# Pro_Trinket_Keyboard_V2.net
KiCad netlist of a schematic drawn in EAGLE
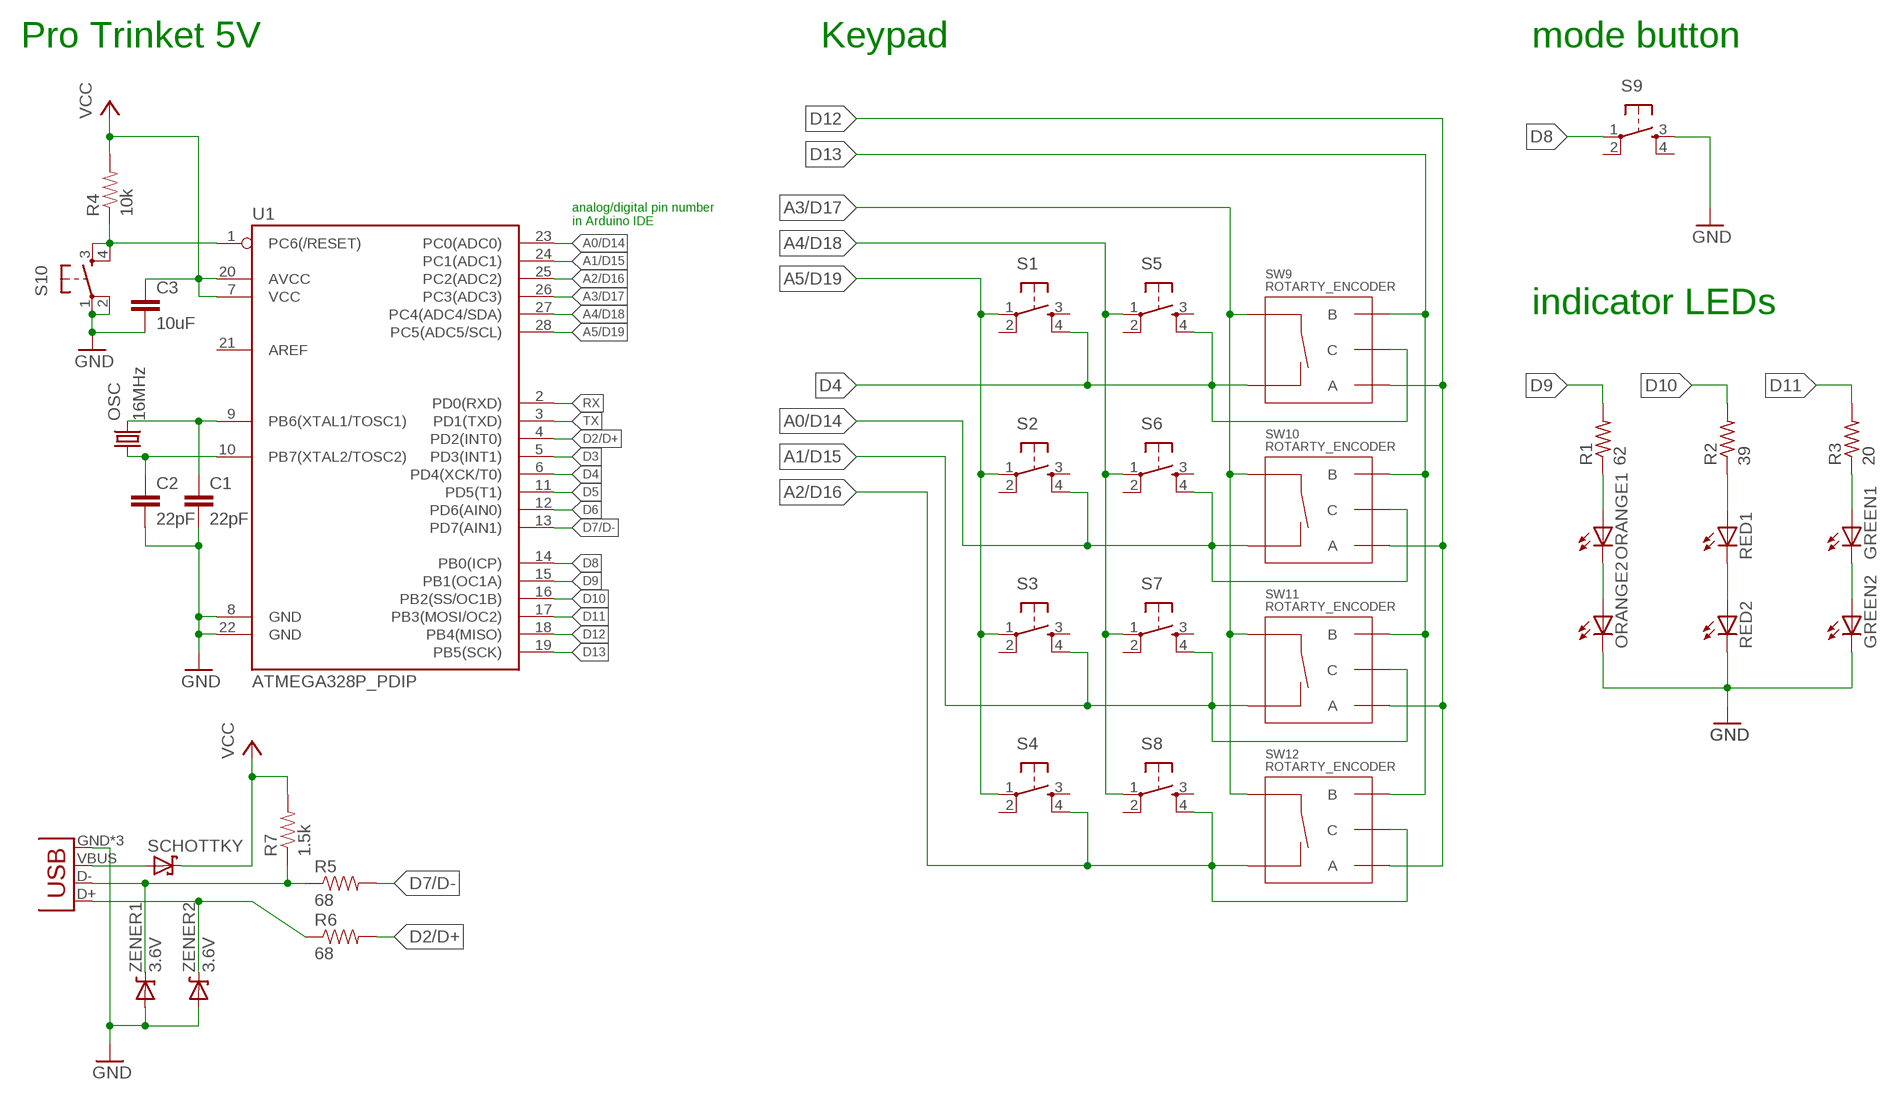
[diagram p0: schematic, sheet 1]

(export (version "E")
  (design (tool "Eeschema 10.0.6"))
  (components
    (comp (ref "C1")
      (value "22pF")
      (footprint "eagle-import:0603-CAP")
      (libsource (lib "eagle-import") (part "22PF-50V-5%(0603)"))
    )
    (comp (ref "C2")
      (value "22pF")
      (footprint "eagle-import:0603-CAP")
      (libsource (lib "eagle-import") (part "22PF-50V-5%(0603)"))
    )
    (comp (ref "C3")
      (value "10uF")
      (footprint "eagle-import:0603-CAP")
      (libsource (lib "eagle-import") (part "10UF-6.3V-20%(0603)"))
    )
    (comp (ref "GREEN1")
      (value "LED3MM")
      (footprint "eagle-import:LED3MM")
      (libsource (lib "eagle-import") (part "LED3MM"))
    )
    (comp (ref "GREEN2")
      (value "LED3MM")
      (footprint "eagle-import:LED3MM")
      (libsource (lib "eagle-import") (part "LED3MM"))
    )
    (comp (ref "JP1")
      (value "USB-MICROB")
      (footprint "eagle-import:USB-MICROB")
      (libsource (lib "eagle-import") (part "USB-MICROB"))
    )
    (comp (ref "ORANGE1")
      (value "LED3MM")
      (footprint "eagle-import:LED3MM")
      (libsource (lib "eagle-import") (part "LED3MM"))
    )
    (comp (ref "ORANGE2")
      (value "LED3MM")
      (footprint "eagle-import:LED3MM")
      (libsource (lib "eagle-import") (part "LED3MM"))
    )
    (comp (ref "OSC")
      (value "16MHz")
      (footprint "eagle-import:HC49_S")
      (libsource (lib "eagle-import") (part "CRYSTALHC49S"))
    )
    (comp (ref "R1")
      (value "62")
      (footprint "eagle-import:0204_7")
      (libsource (lib "eagle-import") (part "R-US_0204/7"))
    )
    (comp (ref "R2")
      (value "39")
      (footprint "eagle-import:0204_7")
      (libsource (lib "eagle-import") (part "R-US_0204/7"))
    )
    (comp (ref "R3")
      (value "20")
      (footprint "eagle-import:0204_7")
      (libsource (lib "eagle-import") (part "R-US_0204/7"))
    )
    (comp (ref "R4")
      (value "10k")
      (footprint "eagle-import:0805")
      (libsource (lib "eagle-import") (part "RESISTOR0805-RES"))
    )
    (comp (ref "R5")
      (value "68")
      (footprint "eagle-import:0805")
      (libsource (lib "eagle-import") (part "RESISTOR0805-RES"))
    )
    (comp (ref "R6")
      (value "68")
      (footprint "eagle-import:0805")
      (libsource (lib "eagle-import") (part "RESISTOR0805-RES"))
    )
    (comp (ref "R7")
      (value "1.5k")
      (footprint "eagle-import:0805")
      (libsource (lib "eagle-import") (part "RESISTOR0805-RES"))
    )
    (comp (ref "RED1")
      (value "LED3MM")
      (footprint "eagle-import:LED3MM")
      (libsource (lib "eagle-import") (part "LED3MM"))
    )
    (comp (ref "RED2")
      (value "LED3MM")
      (footprint "eagle-import:LED3MM")
      (libsource (lib "eagle-import") (part "LED3MM"))
    )
    (comp (ref "S1")
      (value "TAC_SWITCHPTH")
      (footprint "eagle-import:TACTILE-PTH")
      (libsource (lib "eagle-import") (part "TAC_SWITCHPTH"))
    )
    (comp (ref "S2")
      (value "TAC_SWITCHPTH")
      (footprint "eagle-import:TACTILE-PTH")
      (libsource (lib "eagle-import") (part "TAC_SWITCHPTH"))
    )
    (comp (ref "S3")
      (value "TAC_SWITCHPTH")
      (footprint "eagle-import:TACTILE-PTH")
      (libsource (lib "eagle-import") (part "TAC_SWITCHPTH"))
    )
    (comp (ref "S4")
      (value "TAC_SWITCHPTH")
      (footprint "eagle-import:TACTILE-PTH")
      (libsource (lib "eagle-import") (part "TAC_SWITCHPTH"))
    )
    (comp (ref "S5")
      (value "TAC_SWITCHPTH")
      (footprint "eagle-import:TACTILE-PTH")
      (libsource (lib "eagle-import") (part "TAC_SWITCHPTH"))
    )
    (comp (ref "S6")
      (value "TAC_SWITCHPTH")
      (footprint "eagle-import:TACTILE-PTH")
      (libsource (lib "eagle-import") (part "TAC_SWITCHPTH"))
    )
    (comp (ref "S7")
      (value "TAC_SWITCHPTH")
      (footprint "eagle-import:TACTILE-PTH")
      (libsource (lib "eagle-import") (part "TAC_SWITCHPTH"))
    )
    (comp (ref "S8")
      (value "TAC_SWITCHPTH")
      (footprint "eagle-import:TACTILE-PTH")
      (libsource (lib "eagle-import") (part "TAC_SWITCHPTH"))
    )
    (comp (ref "S9")
      (value "TAC_SWITCHPTH")
      (footprint "eagle-import:TACTILE-PTH")
      (libsource (lib "eagle-import") (part "TAC_SWITCHPTH"))
    )
    (comp (ref "S10")
      (value "TAC_SWITCHPTH")
      (footprint "eagle-import:TACTILE-PTH")
      (libsource (lib "eagle-import") (part "TAC_SWITCHPTH"))
    )
    (comp (ref "SCHOTTKY")
      (value "SCHOTTKY-DIODEAG")
      (footprint "eagle-import:AG")
      (libsource (lib "eagle-import") (part "SCHOTTKY-DIODEAG"))
    )
    (comp (ref "SW9")
      (value "ROTARTY_ENCODER")
      (footprint "eagle-import:ROTARY_ENC_PLAIN")
      (libsource (lib "eagle-import") (part "ROTARTY_ENCODER"))
    )
    (comp (ref "SW10")
      (value "ROTARTY_ENCODER")
      (footprint "eagle-import:ROTARY_ENC_PLAIN")
      (libsource (lib "eagle-import") (part "ROTARTY_ENCODER"))
    )
    (comp (ref "SW11")
      (value "ROTARTY_ENCODER")
      (footprint "eagle-import:ROTARY_ENC_PLAIN")
      (libsource (lib "eagle-import") (part "ROTARTY_ENCODER"))
    )
    (comp (ref "SW12")
      (value "ROTARTY_ENCODER")
      (footprint "eagle-import:ROTARY_ENC_PLAIN")
      (libsource (lib "eagle-import") (part "ROTARTY_ENCODER"))
    )
    (comp (ref "U1")
      (value "ATMEGA328P_PDIP")
      (footprint "eagle-import:DIL28-3")
      (libsource (lib "eagle-import") (part "ATMEGA328P_PDIP"))
    )
    (comp (ref "ZENER1")
      (value "3.6V")
      (footprint "eagle-import:SOD-323")
      (libsource (lib "eagle-import") (part "DIODE-ZENER-BZT52"))
    )
    (comp (ref "ZENER2")
      (value "3.6V")
      (footprint "eagle-import:SOD-323")
      (libsource (lib "eagle-import") (part "DIODE-ZENER-BZT52"))
    )
  )
  (nets
    (net (code "1") (name "A0{slash}D14") (class "Default")
      (node (ref "S2") (pin "4") (pinfunction "4_4") (pintype "passive"))
      (node (ref "S6") (pin "4") (pinfunction "4_4") (pintype "passive"))
      (node (ref "SW10") (pin "C") (pinfunction "C_C") (pintype "bidirectional"))
      (node (ref "SW10") (pin "SW-") (pinfunction "SW-_SW-") (pintype "bidirectional"))
      (node (ref "U1") (pin "23") (pinfunction "PC0(ADC0)_23") (pintype "bidirectional"))
    )
    (net (code "2") (name "A1{slash}D15") (class "Default")
      (node (ref "S3") (pin "4") (pinfunction "4_4") (pintype "passive"))
      (node (ref "S7") (pin "4") (pinfunction "4_4") (pintype "passive"))
      (node (ref "SW11") (pin "C") (pinfunction "C_C") (pintype "bidirectional"))
      (node (ref "SW11") (pin "SW-") (pinfunction "SW-_SW-") (pintype "bidirectional"))
      (node (ref "U1") (pin "24") (pinfunction "PC1(ADC1)_24") (pintype "bidirectional"))
    )
    (net (code "3") (name "A2{slash}D16") (class "Default")
      (node (ref "S4") (pin "4") (pinfunction "4_4") (pintype "passive"))
      (node (ref "S8") (pin "4") (pinfunction "4_4") (pintype "passive"))
      (node (ref "SW12") (pin "C") (pinfunction "C_C") (pintype "bidirectional"))
      (node (ref "SW12") (pin "SW-") (pinfunction "SW-_SW-") (pintype "bidirectional"))
      (node (ref "U1") (pin "25") (pinfunction "PC2(ADC2)_25") (pintype "bidirectional"))
    )
    (net (code "4") (name "A3{slash}D17") (class "Default")
      (node (ref "SW10") (pin "SW+") (pinfunction "SW+_SW+") (pintype "bidirectional"))
      (node (ref "SW11") (pin "SW+") (pinfunction "SW+_SW+") (pintype "bidirectional"))
      (node (ref "SW12") (pin "SW+") (pinfunction "SW+_SW+") (pintype "bidirectional"))
      (node (ref "SW9") (pin "SW+") (pinfunction "SW+_SW+") (pintype "bidirectional"))
      (node (ref "U1") (pin "26") (pinfunction "PC3(ADC3)_26") (pintype "bidirectional"))
    )
    (net (code "5") (name "A4{slash}D18") (class "Default")
      (node (ref "S5") (pin "1") (pinfunction "1_1") (pintype "passive"))
      (node (ref "S6") (pin "1") (pinfunction "1_1") (pintype "passive"))
      (node (ref "S7") (pin "1") (pinfunction "1_1") (pintype "passive"))
      (node (ref "S8") (pin "1") (pinfunction "1_1") (pintype "passive"))
      (node (ref "U1") (pin "27") (pinfunction "PC4(ADC4/SDA)_27") (pintype "bidirectional"))
    )
    (net (code "6") (name "A5{slash}D19") (class "Default")
      (node (ref "S1") (pin "1") (pinfunction "1_1") (pintype "passive"))
      (node (ref "S2") (pin "1") (pinfunction "1_1") (pintype "passive"))
      (node (ref "S3") (pin "1") (pinfunction "1_1") (pintype "passive"))
      (node (ref "S4") (pin "1") (pinfunction "1_1") (pintype "passive"))
      (node (ref "U1") (pin "28") (pinfunction "PC5(ADC5/SCL)_28") (pintype "bidirectional"))
    )
    (net (code "7") (name "D2{slash}D+") (class "Default")
      (node (ref "R6") (pin "2") (pinfunction "2_2") (pintype "passive"))
      (node (ref "U1") (pin "4") (pinfunction "PD2(INT0)_4") (pintype "bidirectional"))
    )
    (net (code "8") (name "D3") (class "Default")
      (node (ref "U1") (pin "5") (pinfunction "PD3(INT1)_5") (pintype "bidirectional"))
    )
    (net (code "9") (name "D4") (class "Default")
      (node (ref "S1") (pin "4") (pinfunction "4_4") (pintype "passive"))
      (node (ref "S5") (pin "4") (pinfunction "4_4") (pintype "passive"))
      (node (ref "SW9") (pin "C") (pinfunction "C_C") (pintype "bidirectional"))
      (node (ref "SW9") (pin "SW-") (pinfunction "SW-_SW-") (pintype "bidirectional"))
      (node (ref "U1") (pin "6") (pinfunction "PD4(XCK/T0)_6") (pintype "bidirectional"))
    )
    (net (code "10") (name "D5") (class "Default")
      (node (ref "U1") (pin "11") (pinfunction "PD5(T1)_11") (pintype "bidirectional"))
    )
    (net (code "11") (name "D6") (class "Default")
      (node (ref "U1") (pin "12") (pinfunction "PD6(AIN0)_12") (pintype "bidirectional"))
    )
    (net (code "12") (name "D7{slash}D-") (class "Default")
      (node (ref "R5") (pin "2") (pinfunction "2_2") (pintype "passive"))
      (node (ref "U1") (pin "13") (pinfunction "PD7(AIN1)_13") (pintype "bidirectional"))
    )
    (net (code "13") (name "D8") (class "Default")
      (node (ref "S9") (pin "1") (pinfunction "1_1") (pintype "passive"))
      (node (ref "U1") (pin "14") (pinfunction "PB0(ICP)_14") (pintype "bidirectional"))
    )
    (net (code "14") (name "D9") (class "Default")
      (node (ref "R1") (pin "2") (pinfunction "2_2") (pintype "passive"))
      (node (ref "U1") (pin "15") (pinfunction "PB1(OC1A)_15") (pintype "bidirectional"))
    )
    (net (code "15") (name "D10") (class "Default")
      (node (ref "R2") (pin "2") (pinfunction "2_2") (pintype "passive"))
      (node (ref "U1") (pin "16") (pinfunction "PB2(SS/OC1B)_16") (pintype "bidirectional"))
    )
    (net (code "16") (name "D11") (class "Default")
      (node (ref "R3") (pin "2") (pinfunction "2_2") (pintype "passive"))
      (node (ref "U1") (pin "17") (pinfunction "PB3(MOSI/OC2)_17") (pintype "bidirectional"))
    )
    (net (code "17") (name "D12") (class "Default")
      (node (ref "SW10") (pin "A") (pinfunction "A_A") (pintype "bidirectional"))
      (node (ref "SW11") (pin "A") (pinfunction "A_A") (pintype "bidirectional"))
      (node (ref "SW12") (pin "A") (pinfunction "A_A") (pintype "bidirectional"))
      (node (ref "SW9") (pin "A") (pinfunction "A_A") (pintype "bidirectional"))
      (node (ref "U1") (pin "18") (pinfunction "PB4(MISO)_18") (pintype "bidirectional"))
    )
    (net (code "18") (name "D13") (class "Default")
      (node (ref "SW10") (pin "B") (pinfunction "B_B") (pintype "bidirectional"))
      (node (ref "SW11") (pin "B") (pinfunction "B_B") (pintype "bidirectional"))
      (node (ref "SW12") (pin "B") (pinfunction "B_B") (pintype "bidirectional"))
      (node (ref "SW9") (pin "B") (pinfunction "B_B") (pintype "bidirectional"))
      (node (ref "U1") (pin "19") (pinfunction "PB5(SCK)_19") (pintype "bidirectional"))
    )
    (net (code "19") (name "GND") (class "Default")
      (node (ref "C1") (pin "2") (pinfunction "2_2") (pintype "passive"))
      (node (ref "C2") (pin "2") (pinfunction "2_2") (pintype "passive"))
      (node (ref "C3") (pin "2") (pinfunction "2_2") (pintype "passive"))
      (node (ref "GREEN2") (pin "K") (pinfunction "C_K") (pintype "passive"))
      (node (ref "JP1") (pin "GND") (pinfunction "GND_GND") (pintype "bidirectional"))
      (node (ref "JP1") (pin "MT1") (pinfunction "GND_MT1") (pintype "bidirectional"))
      (node (ref "JP1") (pin "MT2") (pinfunction "GND_MT2") (pintype "bidirectional"))
      (node (ref "ORANGE2") (pin "K") (pinfunction "C_K") (pintype "passive"))
      (node (ref "RED2") (pin "K") (pinfunction "C_K") (pintype "passive"))
      (node (ref "S10") (pin "1") (pinfunction "1_1") (pintype "passive"))
      (node (ref "S10") (pin "2") (pinfunction "2_2") (pintype "passive"))
      (node (ref "S9") (pin "3") (pinfunction "3_3") (pintype "passive"))
      (node (ref "U1") (pin "22") (pinfunction "GND_22") (pintype "bidirectional"))
      (node (ref "U1") (pin "8") (pinfunction "GND_8") (pintype "bidirectional"))
      (node (ref "ZENER1") (pin "A") (pinfunction "A_A") (pintype "passive"))
      (node (ref "ZENER2") (pin "A") (pinfunction "A_A") (pintype "passive"))
    )
    (net (code "20") (name "Net-(GREEN1-C)") (class "Default")
      (node (ref "GREEN1") (pin "K") (pinfunction "C_K") (pintype "passive"))
      (node (ref "GREEN2") (pin "A") (pinfunction "A_A") (pintype "passive"))
    )
    (net (code "21") (name "Net-(GREEN1-PadA)") (class "Default")
      (node (ref "GREEN1") (pin "A") (pinfunction "A_A") (pintype "passive"))
      (node (ref "R3") (pin "1") (pinfunction "1_1") (pintype "passive"))
    )
    (net (code "22") (name "Net-(JP1-PadD+)") (class "Default")
      (node (ref "JP1") (pin "D+") (pinfunction "D+_D+") (pintype "bidirectional"))
      (node (ref "R6") (pin "1") (pinfunction "1_1") (pintype "passive"))
      (node (ref "ZENER2") (pin "C") (pinfunction "C_C") (pintype "passive"))
    )
    (net (code "23") (name "Net-(JP1-PadD-)") (class "Default")
      (node (ref "JP1") (pin "D-") (pinfunction "D-_D-") (pintype "bidirectional"))
      (node (ref "R5") (pin "1") (pinfunction "1_1") (pintype "passive"))
      (node (ref "R7") (pin "1") (pinfunction "1_1") (pintype "passive"))
      (node (ref "ZENER1") (pin "C") (pinfunction "C_C") (pintype "passive"))
    )
    (net (code "24") (name "Net-(JP1-PadVBUS)") (class "Default")
      (node (ref "JP1") (pin "VBUS") (pinfunction "VBUS_VBUS") (pintype "bidirectional"))
      (node (ref "SCHOTTKY") (pin "A") (pinfunction "A_A") (pintype "passive"))
    )
    (net (code "25") (name "Net-(ORANGE1-C)") (class "Default")
      (node (ref "ORANGE1") (pin "K") (pinfunction "C_K") (pintype "passive"))
      (node (ref "ORANGE2") (pin "A") (pinfunction "A_A") (pintype "passive"))
    )
    (net (code "26") (name "Net-(ORANGE1-PadA)") (class "Default")
      (node (ref "ORANGE1") (pin "A") (pinfunction "A_A") (pintype "passive"))
      (node (ref "R1") (pin "1") (pinfunction "1_1") (pintype "passive"))
    )
    (net (code "27") (name "Net-(R2-Pad1)") (class "Default")
      (node (ref "R2") (pin "1") (pinfunction "1_1") (pintype "passive"))
      (node (ref "RED1") (pin "A") (pinfunction "A_A") (pintype "passive"))
    )
    (net (code "28") (name "Net-(RED1-C)") (class "Default")
      (node (ref "RED1") (pin "K") (pinfunction "C_K") (pintype "passive"))
      (node (ref "RED2") (pin "A") (pinfunction "A_A") (pintype "passive"))
    )
    (net (code "29") (name "Net-(U1-PB6(XTAL1{slash}TOSC1))") (class "Default")
      (node (ref "C1") (pin "1") (pinfunction "1_1") (pintype "passive"))
      (node (ref "OSC") (pin "2") (pinfunction "2_2") (pintype "passive"))
      (node (ref "U1") (pin "9") (pinfunction "PB6(XTAL1/TOSC1)_9") (pintype "bidirectional"))
    )
    (net (code "30") (name "Net-(U1-PB7(XTAL2{slash}TOSC2))") (class "Default")
      (node (ref "C2") (pin "1") (pinfunction "1_1") (pintype "passive"))
      (node (ref "OSC") (pin "1") (pinfunction "1_1") (pintype "passive"))
      (node (ref "U1") (pin "10") (pinfunction "PB7(XTAL2/TOSC2)_10") (pintype "bidirectional"))
    )
    (net (code "31") (name "Net-(U1-PC6({slash}RESET))") (class "Default")
      (node (ref "R4") (pin "1") (pinfunction "1_1") (pintype "passive"))
      (node (ref "S10") (pin "3") (pinfunction "3_3") (pintype "passive"))
      (node (ref "S10") (pin "4") (pinfunction "4_4") (pintype "passive"))
      (node (ref "U1") (pin "1") (pinfunction "PC6(/RESET)_1") (pintype "bidirectional"))
    )
    (net (code "32") (name "RX") (class "Default")
      (node (ref "U1") (pin "2") (pinfunction "PD0(RXD)_2") (pintype "bidirectional"))
    )
    (net (code "33") (name "TX") (class "Default")
      (node (ref "U1") (pin "3") (pinfunction "PD1(TXD)_3") (pintype "bidirectional"))
    )
    (net (code "34") (name "VCC") (class "Default")
      (node (ref "C3") (pin "1") (pinfunction "1_1") (pintype "passive"))
      (node (ref "R4") (pin "2") (pinfunction "2_2") (pintype "passive"))
      (node (ref "R7") (pin "2") (pinfunction "2_2") (pintype "passive"))
      (node (ref "SCHOTTKY") (pin "C") (pinfunction "C_C") (pintype "passive"))
      (node (ref "U1") (pin "20") (pinfunction "AVCC_20") (pintype "bidirectional"))
      (node (ref "U1") (pin "7") (pinfunction "VCC_7") (pintype "bidirectional"))
    )
    (net (code "35") (name "unconnected-(S1-Pad2)") (class "Default")
      (node (ref "S1") (pin "2") (pinfunction "2_2") (pintype "passive"))
    )
    (net (code "36") (name "unconnected-(S1-Pad3)") (class "Default")
      (node (ref "S1") (pin "3") (pinfunction "3_3") (pintype "passive"))
    )
    (net (code "37") (name "unconnected-(S2-Pad2)") (class "Default")
      (node (ref "S2") (pin "2") (pinfunction "2_2") (pintype "passive"))
    )
    (net (code "38") (name "unconnected-(S2-Pad3)") (class "Default")
      (node (ref "S2") (pin "3") (pinfunction "3_3") (pintype "passive"))
    )
    (net (code "39") (name "unconnected-(S3-Pad2)") (class "Default")
      (node (ref "S3") (pin "2") (pinfunction "2_2") (pintype "passive"))
    )
    (net (code "40") (name "unconnected-(S3-Pad3)") (class "Default")
      (node (ref "S3") (pin "3") (pinfunction "3_3") (pintype "passive"))
    )
    (net (code "41") (name "unconnected-(S4-Pad2)") (class "Default")
      (node (ref "S4") (pin "2") (pinfunction "2_2") (pintype "passive"))
    )
    (net (code "42") (name "unconnected-(S4-Pad3)") (class "Default")
      (node (ref "S4") (pin "3") (pinfunction "3_3") (pintype "passive"))
    )
    (net (code "43") (name "unconnected-(S5-Pad2)") (class "Default")
      (node (ref "S5") (pin "2") (pinfunction "2_2") (pintype "passive"))
    )
    (net (code "44") (name "unconnected-(S5-Pad3)") (class "Default")
      (node (ref "S5") (pin "3") (pinfunction "3_3") (pintype "passive"))
    )
    (net (code "45") (name "unconnected-(S6-Pad2)") (class "Default")
      (node (ref "S6") (pin "2") (pinfunction "2_2") (pintype "passive"))
    )
    (net (code "46") (name "unconnected-(S6-Pad3)") (class "Default")
      (node (ref "S6") (pin "3") (pinfunction "3_3") (pintype "passive"))
    )
    (net (code "47") (name "unconnected-(S7-Pad2)") (class "Default")
      (node (ref "S7") (pin "2") (pinfunction "2_2") (pintype "passive"))
    )
    (net (code "48") (name "unconnected-(S7-Pad3)") (class "Default")
      (node (ref "S7") (pin "3") (pinfunction "3_3") (pintype "passive"))
    )
    (net (code "49") (name "unconnected-(S8-Pad2)") (class "Default")
      (node (ref "S8") (pin "2") (pinfunction "2_2") (pintype "passive"))
    )
    (net (code "50") (name "unconnected-(S8-Pad3)") (class "Default")
      (node (ref "S8") (pin "3") (pinfunction "3_3") (pintype "passive"))
    )
    (net (code "51") (name "unconnected-(S9-Pad2)") (class "Default")
      (node (ref "S9") (pin "2") (pinfunction "2_2") (pintype "passive"))
    )
    (net (code "52") (name "unconnected-(S9-Pad4)") (class "Default")
      (node (ref "S9") (pin "4") (pinfunction "4_4") (pintype "passive"))
    )
    (net (code "53") (name "unconnected-(U1-AREF-Pad21)") (class "Default")
      (node (ref "U1") (pin "21") (pinfunction "AREF_21") (pintype "bidirectional"))
    )
  )
)
